# Sensor.net
KiCad netlist of a schematic drawn in Altium Designer
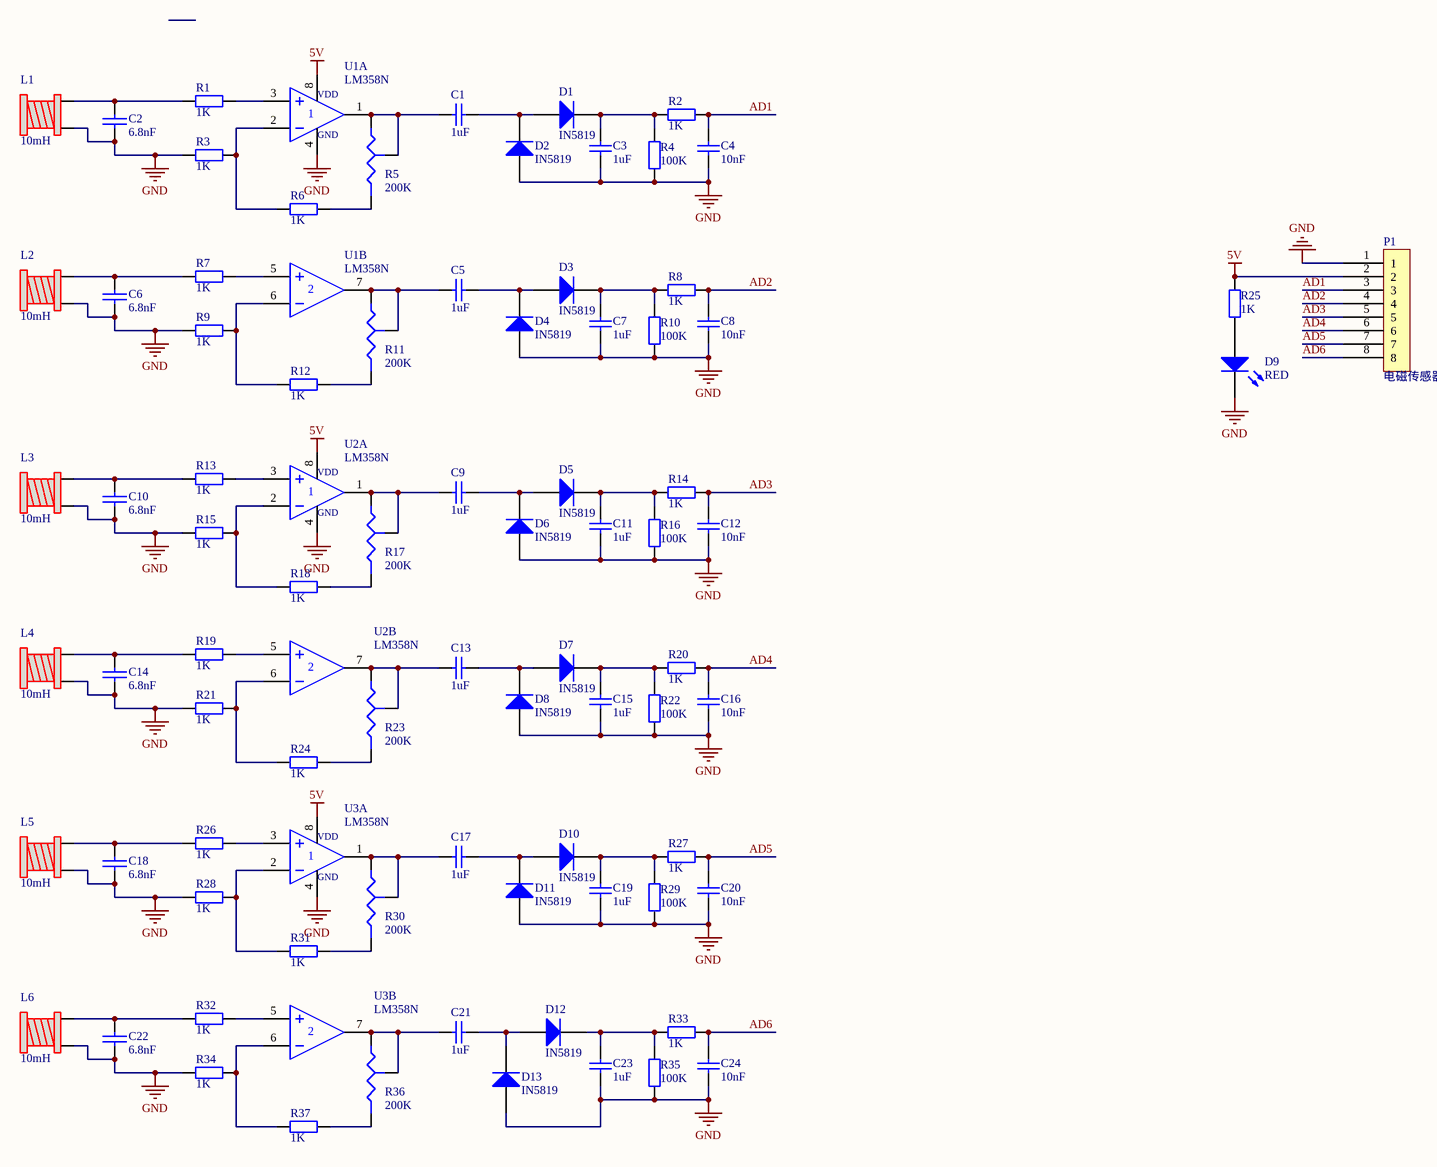
[diagram p0: Sensor.SchDoc]

(export (version "E")
  (design (tool "Eeschema 10.0.6"))
  (components
    (comp (ref "C1") (value "1uF") (footprint "0603C") (libsource (lib "1209Lab") (part "CAP")))
    (comp (ref "C2")
      (value "6.8nF")
      (footprint "0603C")
      (description "Capacitor")
      (libsource (lib "电磁放大器模块") (part "6.8μF"))
    )
    (comp (ref "C3") (value "1uF") (footprint "0603C") (libsource (lib "1209Lab") (part "CAP")))
    (comp (ref "C4") (value "10nF") (footprint "0603C") (libsource (lib "1209Lab") (part "CAP")))
    (comp (ref "C5") (value "1uF") (footprint "0603C") (libsource (lib "1209Lab") (part "CAP")))
    (comp (ref "C6")
      (value "6.8nF")
      (footprint "0603C")
      (description "Capacitor")
      (libsource (lib "电磁放大器模块") (part "6.8μF"))
    )
    (comp (ref "C7") (value "1uF") (footprint "0603C") (libsource (lib "1209Lab") (part "CAP")))
    (comp (ref "C8") (value "10nF") (footprint "0603C") (libsource (lib "1209Lab") (part "CAP")))
    (comp (ref "C9") (value "1uF") (footprint "0603C") (libsource (lib "1209Lab") (part "CAP")))
    (comp (ref "C10")
      (value "6.8nF")
      (footprint "0603C")
      (description "Capacitor")
      (libsource (lib "电磁放大器模块") (part "6.8μF"))
    )
    (comp (ref "C11") (value "1uF") (footprint "0603C") (libsource (lib "1209Lab") (part "CAP")))
    (comp (ref "C12") (value "10nF") (footprint "0603C") (libsource (lib "1209Lab") (part "CAP")))
    (comp (ref "C13") (value "1uF") (footprint "0603C") (libsource (lib "1209Lab") (part "CAP")))
    (comp (ref "C14")
      (value "6.8nF")
      (footprint "0603C")
      (description "Capacitor")
      (libsource (lib "电磁放大器模块") (part "6.8μF"))
    )
    (comp (ref "C15") (value "1uF") (footprint "0603C") (libsource (lib "1209Lab") (part "CAP")))
    (comp (ref "C16") (value "10nF") (footprint "0603C") (libsource (lib "1209Lab") (part "CAP")))
    (comp (ref "C17") (value "1uF") (footprint "0603C") (libsource (lib "1209Lab") (part "CAP")))
    (comp (ref "C18")
      (value "6.8nF")
      (footprint "0603C")
      (description "Capacitor")
      (libsource (lib "电磁放大器模块") (part "6.8μF"))
    )
    (comp (ref "C19") (value "1uF") (footprint "0603C") (libsource (lib "1209Lab") (part "CAP")))
    (comp (ref "C20") (value "10nF") (footprint "0603C") (libsource (lib "1209Lab") (part "CAP")))
    (comp (ref "C21") (value "1uF") (footprint "0603C") (libsource (lib "1209Lab") (part "CAP")))
    (comp (ref "C22")
      (value "6.8nF")
      (footprint "0603C")
      (description "Capacitor")
      (libsource (lib "电磁放大器模块") (part "6.8μF"))
    )
    (comp (ref "C23") (value "1uF") (footprint "0603C") (libsource (lib "1209Lab") (part "CAP")))
    (comp (ref "C24") (value "10nF") (footprint "0603C") (libsource (lib "1209Lab") (part "CAP")))
    (comp (ref "D1")
      (value "IN5819")
      (footprint "DL-41 - duplicate")
      (description "Default Diode")
      (libsource (lib "MOS motor driving module ") (part "Diode"))
    )
    (comp (ref "D2")
      (value "IN5819")
      (footprint "DL-41 - duplicate")
      (description "Default Diode")
      (libsource (lib "MOS motor driving module ") (part "Diode"))
    )
    (comp (ref "D3")
      (value "IN5819")
      (footprint "DL-41 - duplicate")
      (description "Default Diode")
      (libsource (lib "MOS motor driving module ") (part "Diode"))
    )
    (comp (ref "D4")
      (value "IN5819")
      (footprint "DL-41 - duplicate")
      (description "Default Diode")
      (libsource (lib "MOS motor driving module ") (part "Diode"))
    )
    (comp (ref "D5")
      (value "IN5819")
      (footprint "DL-41 - duplicate")
      (description "Default Diode")
      (libsource (lib "MOS motor driving module ") (part "Diode"))
    )
    (comp (ref "D6")
      (value "IN5819")
      (footprint "DL-41 - duplicate")
      (description "Default Diode")
      (libsource (lib "MOS motor driving module ") (part "Diode"))
    )
    (comp (ref "D7")
      (value "IN5819")
      (footprint "DL-41 - duplicate")
      (description "Default Diode")
      (libsource (lib "MOS motor driving module ") (part "Diode"))
    )
    (comp (ref "D8")
      (value "IN5819")
      (footprint "DL-41 - duplicate")
      (description "Default Diode")
      (libsource (lib "MOS motor driving module ") (part "Diode"))
    )
    (comp (ref "D9")
      (value "RED")
      (footprint "0805LED")
      (description "Typical RED, GREEN, YELLOW, AMBER GaAs LED")
      (fields (field (name "PUBLISHER") "Altium Limited"))
      (libsource (lib "MOS motor driving module ") (part "LED2"))
    )
    (comp (ref "D10")
      (value "IN5819")
      (footprint "DL-41 - duplicate")
      (description "Default Diode")
      (libsource (lib "MOS motor driving module ") (part "Diode"))
    )
    (comp (ref "D11")
      (value "IN5819")
      (footprint "DL-41 - duplicate")
      (description "Default Diode")
      (libsource (lib "MOS motor driving module ") (part "Diode"))
    )
    (comp (ref "D12")
      (value "IN5819")
      (footprint "DL-41 - duplicate")
      (description "Default Diode")
      (libsource (lib "MOS motor driving module ") (part "Diode"))
    )
    (comp (ref "D13")
      (value "IN5819")
      (footprint "DL-41 - duplicate")
      (description "Default Diode")
      (libsource (lib "MOS motor driving module ") (part "Diode"))
    )
    (comp (ref "L1") (value "10mH") (footprint "6X8mm电感") (libsource (lib "电磁放大器模块") (part "Inductor_1")))
    (comp (ref "L2") (value "10mH") (footprint "6X8mm电感") (libsource (lib "电磁放大器模块") (part "Inductor_1")))
    (comp (ref "L3") (value "10mH") (footprint "6X8mm电感") (libsource (lib "电磁放大器模块") (part "Inductor_1")))
    (comp (ref "L4") (value "10mH") (footprint "6X8mm电感") (libsource (lib "电磁放大器模块") (part "Inductor_1")))
    (comp (ref "L5") (value "10mH") (footprint "6X8mm电感") (libsource (lib "电磁放大器模块") (part "Inductor_1")))
    (comp (ref "L6") (value "10mH") (footprint "6X8mm电感") (libsource (lib "电磁放大器模块") (part "Inductor_1")))
    (comp (ref "P1")
      (value "电磁传感器")
      (footprint "XH2.54_8P")
      (description "Header, 4-Pin, Dual row")
      (fields (field (name "PUBLISHER") "Altium Limited"))
      (libsource (lib "蓝宙电子锋速系列主板封装库") (part "Header 8X1A"))
    )
    (comp (ref "R1")
      (value "1K")
      (footprint "0603-1")
      (description "Resistor贴片封装")
      (fields (field (name "Comment") "Res2") (field (name "PUBLISHER") "Altium Limited"))
      (libsource (lib "My") (part "Res2"))
    )
    (comp (ref "R2")
      (value "1K")
      (footprint "0603-1")
      (description "Resistor贴片封装")
      (fields (field (name "Comment") "Res2") (field (name "PUBLISHER") "Altium Limited"))
      (libsource (lib "") (part "Res2_1"))
    )
    (comp (ref "R3")
      (value "1K")
      (footprint "0603-1")
      (description "Resistor贴片封装")
      (fields (field (name "Comment") "Res2") (field (name "PUBLISHER") "Altium Limited"))
      (libsource (lib "My") (part "Res2"))
    )
    (comp (ref "R4")
      (value "100K")
      (footprint "0603-1")
      (description "Resistor贴片封装")
      (fields (field (name "Comment") "Res2") (field (name "PUBLISHER") "Altium Limited"))
      (libsource (lib "") (part "Res2_2"))
    )
    (comp (ref "R5") (value "200K") (footprint "VR_3362P") (libsource (lib "1209Lab") (part "RES-ADJ")))
    (comp (ref "R6")
      (value "1K")
      (footprint "0603-1")
      (description "Resistor贴片封装")
      (fields (field (name "Comment") "Res2") (field (name "PUBLISHER") "Altium Limited"))
      (libsource (lib "My") (part "Res2"))
    )
    (comp (ref "R7")
      (value "1K")
      (footprint "0603-1")
      (description "Resistor贴片封装")
      (fields (field (name "Comment") "Res2") (field (name "PUBLISHER") "Altium Limited"))
      (libsource (lib "My") (part "Res2"))
    )
    (comp (ref "R8")
      (value "1K")
      (footprint "0603-1")
      (description "Resistor贴片封装")
      (fields (field (name "Comment") "Res2") (field (name "PUBLISHER") "Altium Limited"))
      (libsource (lib "") (part "Res2_1"))
    )
    (comp (ref "R9")
      (value "1K")
      (footprint "0603-1")
      (description "Resistor贴片封装")
      (fields (field (name "Comment") "Res2") (field (name "PUBLISHER") "Altium Limited"))
      (libsource (lib "My") (part "Res2"))
    )
    (comp (ref "R10")
      (value "100K")
      (footprint "0603-1")
      (description "Resistor贴片封装")
      (fields (field (name "Comment") "Res2") (field (name "PUBLISHER") "Altium Limited"))
      (libsource (lib "") (part "Res2_2"))
    )
    (comp (ref "R11") (value "200K") (footprint "VR_3362P") (libsource (lib "1209Lab") (part "RES-ADJ")))
    (comp (ref "R12")
      (value "1K")
      (footprint "0603-1")
      (description "Resistor贴片封装")
      (fields (field (name "Comment") "Res2") (field (name "PUBLISHER") "Altium Limited"))
      (libsource (lib "My") (part "Res2"))
    )
    (comp (ref "R13")
      (value "1K")
      (footprint "0603-1")
      (description "Resistor贴片封装")
      (fields (field (name "Comment") "Res2") (field (name "PUBLISHER") "Altium Limited"))
      (libsource (lib "My") (part "Res2"))
    )
    (comp (ref "R14")
      (value "1K")
      (footprint "0603-1")
      (description "Resistor贴片封装")
      (fields (field (name "Comment") "Res2") (field (name "PUBLISHER") "Altium Limited"))
      (libsource (lib "") (part "Res2_1"))
    )
    (comp (ref "R15")
      (value "1K")
      (footprint "0603-1")
      (description "Resistor贴片封装")
      (fields (field (name "Comment") "Res2") (field (name "PUBLISHER") "Altium Limited"))
      (libsource (lib "My") (part "Res2"))
    )
    (comp (ref "R16")
      (value "100K")
      (footprint "0603-1")
      (description "Resistor贴片封装")
      (fields (field (name "Comment") "Res2") (field (name "PUBLISHER") "Altium Limited"))
      (libsource (lib "") (part "Res2_2"))
    )
    (comp (ref "R17") (value "200K") (footprint "VR_3362P") (libsource (lib "1209Lab") (part "RES-ADJ")))
    (comp (ref "R18")
      (value "1K")
      (footprint "0603-1")
      (description "Resistor贴片封装")
      (fields (field (name "Comment") "Res2") (field (name "PUBLISHER") "Altium Limited"))
      (libsource (lib "My") (part "Res2"))
    )
    (comp (ref "R19")
      (value "1K")
      (footprint "0603-1")
      (description "Resistor贴片封装")
      (fields (field (name "Comment") "Res2") (field (name "PUBLISHER") "Altium Limited"))
      (libsource (lib "My") (part "Res2"))
    )
    (comp (ref "R20")
      (value "1K")
      (footprint "0603-1")
      (description "Resistor贴片封装")
      (fields (field (name "Comment") "Res2") (field (name "PUBLISHER") "Altium Limited"))
      (libsource (lib "") (part "Res2_1"))
    )
    (comp (ref "R21")
      (value "1K")
      (footprint "0603-1")
      (description "Resistor贴片封装")
      (fields (field (name "Comment") "Res2") (field (name "PUBLISHER") "Altium Limited"))
      (libsource (lib "My") (part "Res2"))
    )
    (comp (ref "R22")
      (value "100K")
      (footprint "0603-1")
      (description "Resistor贴片封装")
      (fields (field (name "Comment") "Res2") (field (name "PUBLISHER") "Altium Limited"))
      (libsource (lib "") (part "Res2_2"))
    )
    (comp (ref "R23") (value "200K") (footprint "VR_3362P") (libsource (lib "1209Lab") (part "RES-ADJ")))
    (comp (ref "R24")
      (value "1K")
      (footprint "0603-1")
      (description "Resistor贴片封装")
      (fields (field (name "Comment") "Res2") (field (name "PUBLISHER") "Altium Limited"))
      (libsource (lib "My") (part "Res2"))
    )
    (comp (ref "R25")
      (value "1K")
      (footprint "0603-1")
      (description "Resistor贴片封装")
      (fields (field (name "Comment") "Res2") (field (name "PUBLISHER") "Altium Limited"))
      (libsource (lib "") (part "Res2_3"))
    )
    (comp (ref "R26")
      (value "1K")
      (footprint "0603-1")
      (description "Resistor贴片封装")
      (fields (field (name "Comment") "Res2") (field (name "PUBLISHER") "Altium Limited"))
      (libsource (lib "My") (part "Res2"))
    )
    (comp (ref "R27")
      (value "1K")
      (footprint "0603-1")
      (description "Resistor贴片封装")
      (fields (field (name "Comment") "Res2") (field (name "PUBLISHER") "Altium Limited"))
      (libsource (lib "") (part "Res2_1"))
    )
    (comp (ref "R28")
      (value "1K")
      (footprint "0603-1")
      (description "Resistor贴片封装")
      (fields (field (name "Comment") "Res2") (field (name "PUBLISHER") "Altium Limited"))
      (libsource (lib "My") (part "Res2"))
    )
    (comp (ref "R29")
      (value "100K")
      (footprint "0603-1")
      (description "Resistor贴片封装")
      (fields (field (name "Comment") "Res2") (field (name "PUBLISHER") "Altium Limited"))
      (libsource (lib "") (part "Res2_2"))
    )
    (comp (ref "R30") (value "200K") (footprint "VR_3362P") (libsource (lib "1209Lab") (part "RES-ADJ")))
    (comp (ref "R31")
      (value "1K")
      (footprint "0603-1")
      (description "Resistor贴片封装")
      (fields (field (name "Comment") "Res2") (field (name "PUBLISHER") "Altium Limited"))
      (libsource (lib "My") (part "Res2"))
    )
    (comp (ref "R32")
      (value "1K")
      (footprint "0603-1")
      (description "Resistor贴片封装")
      (fields (field (name "Comment") "Res2") (field (name "PUBLISHER") "Altium Limited"))
      (libsource (lib "My") (part "Res2"))
    )
    (comp (ref "R33")
      (value "1K")
      (footprint "0603-1")
      (description "Resistor贴片封装")
      (fields (field (name "Comment") "Res2") (field (name "PUBLISHER") "Altium Limited"))
      (libsource (lib "") (part "Res2_1"))
    )
    (comp (ref "R34")
      (value "1K")
      (footprint "0603-1")
      (description "Resistor贴片封装")
      (fields (field (name "Comment") "Res2") (field (name "PUBLISHER") "Altium Limited"))
      (libsource (lib "My") (part "Res2"))
    )
    (comp (ref "R35")
      (value "100K")
      (footprint "0603-1")
      (description "Resistor贴片封装")
      (fields (field (name "Comment") "Res2") (field (name "PUBLISHER") "Altium Limited"))
      (libsource (lib "") (part "Res2_2"))
    )
    (comp (ref "R36") (value "200K") (footprint "VR_3362P") (libsource (lib "1209Lab") (part "RES-ADJ")))
    (comp (ref "R37")
      (value "1K")
      (footprint "0603-1")
      (description "Resistor贴片封装")
      (fields (field (name "Comment") "Res2") (field (name "PUBLISHER") "Altium Limited"))
      (libsource (lib "My") (part "Res2"))
    )
    (comp (ref "U1")
      (value "LM358N")
      (footprint "SOIC-8")
      (description "Dual Low-Power Operational Amplifier")
      (libsource (lib "电磁放大器模块") (part "LM358N"))
    )
    (comp (ref "U2")
      (value "LM358N")
      (footprint "SOIC-8")
      (description "Dual Low-Power Operational Amplifier")
      (libsource (lib "电磁放大器模块") (part "LM358N"))
    )
    (comp (ref "U3")
      (value "LM358N")
      (footprint "SOIC-8")
      (description "Dual Low-Power Operational Amplifier")
      (libsource (lib "电磁放大器模块") (part "LM358N"))
    )
  )
  (nets
    (net (code "1") (name "/AD1") (class "Default")
      (node (ref "C4") (pin "1") (pinfunction "1_1") (pintype "passive"))
      (node (ref "P1") (pin "3") (pinfunction "3_3") (pintype "passive"))
      (node (ref "R2") (pin "1") (pinfunction "1_1") (pintype "passive"))
    )
    (net (code "2") (name "/AD2") (class "Default")
      (node (ref "C8") (pin "1") (pinfunction "1_1") (pintype "passive"))
      (node (ref "P1") (pin "4") (pinfunction "4_4") (pintype "passive"))
      (node (ref "R8") (pin "1") (pinfunction "1_1") (pintype "passive"))
    )
    (net (code "3") (name "/AD3") (class "Default")
      (node (ref "C12") (pin "1") (pinfunction "1_1") (pintype "passive"))
      (node (ref "P1") (pin "5") (pinfunction "5_5") (pintype "passive"))
      (node (ref "R14") (pin "1") (pinfunction "1_1") (pintype "passive"))
    )
    (net (code "4") (name "/AD4") (class "Default")
      (node (ref "C16") (pin "1") (pinfunction "1_1") (pintype "passive"))
      (node (ref "P1") (pin "6") (pinfunction "6_6") (pintype "passive"))
      (node (ref "R20") (pin "1") (pinfunction "1_1") (pintype "passive"))
    )
    (net (code "5") (name "/AD5") (class "Default")
      (node (ref "C20") (pin "1") (pinfunction "1_1") (pintype "passive"))
      (node (ref "P1") (pin "7") (pinfunction "7_7") (pintype "passive"))
      (node (ref "R27") (pin "1") (pinfunction "1_1") (pintype "passive"))
    )
    (net (code "6") (name "/AD6") (class "Default")
      (node (ref "C24") (pin "1") (pinfunction "1_1") (pintype "passive"))
      (node (ref "P1") (pin "8") (pinfunction "8_8") (pintype "passive"))
      (node (ref "R33") (pin "1") (pinfunction "1_1") (pintype "passive"))
    )
    (net (code "7") (name "5V") (class "Default")
      (node (ref "P1") (pin "2") (pinfunction "2_2") (pintype "passive"))
      (node (ref "R25") (pin "1") (pinfunction "1_1") (pintype "passive"))
      (node (ref "U1") (pin "8") (pinfunction "VDD_8") (pintype "passive"))
      (node (ref "U2") (pin "8") (pinfunction "VDD_8") (pintype "passive"))
      (node (ref "U3") (pin "8") (pinfunction "VDD_8") (pintype "passive"))
    )
    (net (code "8") (name "GND") (class "Default")
      (node (ref "C10") (pin "2") (pinfunction "2_2") (pintype "passive"))
      (node (ref "C11") (pin "2") (pinfunction "2_2") (pintype "passive"))
      (node (ref "C12") (pin "2") (pinfunction "2_2") (pintype "passive"))
      (node (ref "C14") (pin "2") (pinfunction "2_2") (pintype "passive"))
      (node (ref "C15") (pin "2") (pinfunction "2_2") (pintype "passive"))
      (node (ref "C16") (pin "2") (pinfunction "2_2") (pintype "passive"))
      (node (ref "C18") (pin "2") (pinfunction "2_2") (pintype "passive"))
      (node (ref "C19") (pin "2") (pinfunction "2_2") (pintype "passive"))
      (node (ref "C2") (pin "2") (pinfunction "2_2") (pintype "passive"))
      (node (ref "C20") (pin "2") (pinfunction "2_2") (pintype "passive"))
      (node (ref "C22") (pin "2") (pinfunction "2_2") (pintype "passive"))
      (node (ref "C23") (pin "2") (pinfunction "2_2") (pintype "passive"))
      (node (ref "C24") (pin "2") (pinfunction "2_2") (pintype "passive"))
      (node (ref "C3") (pin "2") (pinfunction "2_2") (pintype "passive"))
      (node (ref "C4") (pin "2") (pinfunction "2_2") (pintype "passive"))
      (node (ref "C6") (pin "2") (pinfunction "2_2") (pintype "passive"))
      (node (ref "C7") (pin "2") (pinfunction "2_2") (pintype "passive"))
      (node (ref "C8") (pin "2") (pinfunction "2_2") (pintype "passive"))
      (node (ref "D11") (pin "1") (pinfunction "A_1") (pintype "passive"))
      (node (ref "D13") (pin "1") (pinfunction "A_1") (pintype "passive"))
      (node (ref "D2") (pin "1") (pinfunction "A_1") (pintype "passive"))
      (node (ref "D4") (pin "1") (pinfunction "A_1") (pintype "passive"))
      (node (ref "D6") (pin "1") (pinfunction "A_1") (pintype "passive"))
      (node (ref "D8") (pin "1") (pinfunction "A_1") (pintype "passive"))
      (node (ref "D9") (pin "2") (pinfunction "K_2") (pintype "passive"))
      (node (ref "L1") (pin "1") (pinfunction "1_1") (pintype "passive"))
      (node (ref "L2") (pin "1") (pinfunction "1_1") (pintype "passive"))
      (node (ref "L3") (pin "1") (pinfunction "1_1") (pintype "passive"))
      (node (ref "L4") (pin "1") (pinfunction "1_1") (pintype "passive"))
      (node (ref "L5") (pin "1") (pinfunction "1_1") (pintype "passive"))
      (node (ref "L6") (pin "1") (pinfunction "1_1") (pintype "passive"))
      (node (ref "P1") (pin "1") (pinfunction "1_1") (pintype "passive"))
      (node (ref "R10") (pin "1") (pinfunction "1_1") (pintype "passive"))
      (node (ref "R15") (pin "1") (pinfunction "1_1") (pintype "passive"))
      (node (ref "R16") (pin "1") (pinfunction "1_1") (pintype "passive"))
      (node (ref "R21") (pin "1") (pinfunction "1_1") (pintype "passive"))
      (node (ref "R22") (pin "1") (pinfunction "1_1") (pintype "passive"))
      (node (ref "R28") (pin "1") (pinfunction "1_1") (pintype "passive"))
      (node (ref "R29") (pin "1") (pinfunction "1_1") (pintype "passive"))
      (node (ref "R3") (pin "1") (pinfunction "1_1") (pintype "passive"))
      (node (ref "R34") (pin "1") (pinfunction "1_1") (pintype "passive"))
      (node (ref "R35") (pin "1") (pinfunction "1_1") (pintype "passive"))
      (node (ref "R4") (pin "1") (pinfunction "1_1") (pintype "passive"))
      (node (ref "R9") (pin "1") (pinfunction "1_1") (pintype "passive"))
      (node (ref "U1") (pin "4") (pinfunction "GND_4") (pintype "passive"))
      (node (ref "U2") (pin "4") (pinfunction "GND_4") (pintype "passive"))
      (node (ref "U3") (pin "4") (pinfunction "GND_4") (pintype "passive"))
    )
    (net (code "9") (name "Net-(C2-Pad1)") (class "Default")
      (node (ref "C2") (pin "1") (pinfunction "1_1") (pintype "passive"))
      (node (ref "L1") (pin "2") (pinfunction "2_2") (pintype "passive"))
      (node (ref "R1") (pin "1") (pinfunction "1_1") (pintype "passive"))
    )
    (net (code "10") (name "Net-(C6-Pad1)") (class "Default")
      (node (ref "C6") (pin "1") (pinfunction "1_1") (pintype "passive"))
      (node (ref "L2") (pin "2") (pinfunction "2_2") (pintype "passive"))
      (node (ref "R7") (pin "1") (pinfunction "1_1") (pintype "passive"))
    )
    (net (code "11") (name "Net-(C10-Pad1)") (class "Default")
      (node (ref "C10") (pin "1") (pinfunction "1_1") (pintype "passive"))
      (node (ref "L3") (pin "2") (pinfunction "2_2") (pintype "passive"))
      (node (ref "R13") (pin "1") (pinfunction "1_1") (pintype "passive"))
    )
    (net (code "12") (name "Net-(C14-Pad1)") (class "Default")
      (node (ref "C14") (pin "1") (pinfunction "1_1") (pintype "passive"))
      (node (ref "L4") (pin "2") (pinfunction "2_2") (pintype "passive"))
      (node (ref "R19") (pin "1") (pinfunction "1_1") (pintype "passive"))
    )
    (net (code "13") (name "Net-(C18-Pad1)") (class "Default")
      (node (ref "C18") (pin "1") (pinfunction "1_1") (pintype "passive"))
      (node (ref "L5") (pin "2") (pinfunction "2_2") (pintype "passive"))
      (node (ref "R26") (pin "1") (pinfunction "1_1") (pintype "passive"))
    )
    (net (code "14") (name "Net-(C22-Pad1)") (class "Default")
      (node (ref "C22") (pin "1") (pinfunction "1_1") (pintype "passive"))
      (node (ref "L6") (pin "2") (pinfunction "2_2") (pintype "passive"))
      (node (ref "R32") (pin "1") (pinfunction "1_1") (pintype "passive"))
    )
    (net (code "15") (name "Net-(D1-A)") (class "Default")
      (node (ref "C1") (pin "1") (pinfunction "1_1") (pintype "passive"))
      (node (ref "D1") (pin "1") (pinfunction "A_1") (pintype "passive"))
      (node (ref "D2") (pin "2") (pinfunction "K_2") (pintype "passive"))
    )
    (net (code "16") (name "Net-(D1-K)") (class "Default")
      (node (ref "C3") (pin "1") (pinfunction "1_1") (pintype "passive"))
      (node (ref "D1") (pin "2") (pinfunction "K_2") (pintype "passive"))
      (node (ref "R2") (pin "2") (pinfunction "2_2") (pintype "passive"))
      (node (ref "R4") (pin "2") (pinfunction "2_2") (pintype "passive"))
    )
    (net (code "17") (name "Net-(D3-A)") (class "Default")
      (node (ref "C5") (pin "1") (pinfunction "1_1") (pintype "passive"))
      (node (ref "D3") (pin "1") (pinfunction "A_1") (pintype "passive"))
      (node (ref "D4") (pin "2") (pinfunction "K_2") (pintype "passive"))
    )
    (net (code "18") (name "Net-(D3-K)") (class "Default")
      (node (ref "C7") (pin "1") (pinfunction "1_1") (pintype "passive"))
      (node (ref "D3") (pin "2") (pinfunction "K_2") (pintype "passive"))
      (node (ref "R10") (pin "2") (pinfunction "2_2") (pintype "passive"))
      (node (ref "R8") (pin "2") (pinfunction "2_2") (pintype "passive"))
    )
    (net (code "19") (name "Net-(D5-A)") (class "Default")
      (node (ref "C9") (pin "1") (pinfunction "1_1") (pintype "passive"))
      (node (ref "D5") (pin "1") (pinfunction "A_1") (pintype "passive"))
      (node (ref "D6") (pin "2") (pinfunction "K_2") (pintype "passive"))
    )
    (net (code "20") (name "Net-(D5-K)") (class "Default")
      (node (ref "C11") (pin "1") (pinfunction "1_1") (pintype "passive"))
      (node (ref "D5") (pin "2") (pinfunction "K_2") (pintype "passive"))
      (node (ref "R14") (pin "2") (pinfunction "2_2") (pintype "passive"))
      (node (ref "R16") (pin "2") (pinfunction "2_2") (pintype "passive"))
    )
    (net (code "21") (name "Net-(D7-A)") (class "Default")
      (node (ref "C13") (pin "1") (pinfunction "1_1") (pintype "passive"))
      (node (ref "D7") (pin "1") (pinfunction "A_1") (pintype "passive"))
      (node (ref "D8") (pin "2") (pinfunction "K_2") (pintype "passive"))
    )
    (net (code "22") (name "Net-(D7-K)") (class "Default")
      (node (ref "C15") (pin "1") (pinfunction "1_1") (pintype "passive"))
      (node (ref "D7") (pin "2") (pinfunction "K_2") (pintype "passive"))
      (node (ref "R20") (pin "2") (pinfunction "2_2") (pintype "passive"))
      (node (ref "R22") (pin "2") (pinfunction "2_2") (pintype "passive"))
    )
    (net (code "23") (name "Net-(D9-A)") (class "Default")
      (node (ref "D9") (pin "1") (pinfunction "A_1") (pintype "passive"))
      (node (ref "R25") (pin "2") (pinfunction "2_2") (pintype "passive"))
    )
    (net (code "24") (name "Net-(D10-A)") (class "Default")
      (node (ref "C17") (pin "1") (pinfunction "1_1") (pintype "passive"))
      (node (ref "D10") (pin "1") (pinfunction "A_1") (pintype "passive"))
      (node (ref "D11") (pin "2") (pinfunction "K_2") (pintype "passive"))
    )
    (net (code "25") (name "Net-(D10-K)") (class "Default")
      (node (ref "C19") (pin "1") (pinfunction "1_1") (pintype "passive"))
      (node (ref "D10") (pin "2") (pinfunction "K_2") (pintype "passive"))
      (node (ref "R27") (pin "2") (pinfunction "2_2") (pintype "passive"))
      (node (ref "R29") (pin "2") (pinfunction "2_2") (pintype "passive"))
    )
    (net (code "26") (name "Net-(D12-A)") (class "Default")
      (node (ref "C21") (pin "1") (pinfunction "1_1") (pintype "passive"))
      (node (ref "D12") (pin "1") (pinfunction "A_1") (pintype "passive"))
      (node (ref "D13") (pin "2") (pinfunction "K_2") (pintype "passive"))
    )
    (net (code "27") (name "Net-(D12-K)") (class "Default")
      (node (ref "C23") (pin "1") (pinfunction "1_1") (pintype "passive"))
      (node (ref "D12") (pin "2") (pinfunction "K_2") (pintype "passive"))
      (node (ref "R33") (pin "2") (pinfunction "2_2") (pintype "passive"))
      (node (ref "R35") (pin "2") (pinfunction "2_2") (pintype "passive"))
    )
    (net (code "28") (name "Net-(R5-Pad3)") (class "Default")
      (node (ref "R5") (pin "3") (pinfunction "3_3") (pintype "passive"))
      (node (ref "R6") (pin "2") (pinfunction "2_2") (pintype "passive"))
    )
    (net (code "29") (name "Net-(R11-Pad3)") (class "Default")
      (node (ref "R11") (pin "3") (pinfunction "3_3") (pintype "passive"))
      (node (ref "R12") (pin "2") (pinfunction "2_2") (pintype "passive"))
    )
    (net (code "30") (name "Net-(R17-Pad3)") (class "Default")
      (node (ref "R17") (pin "3") (pinfunction "3_3") (pintype "passive"))
      (node (ref "R18") (pin "2") (pinfunction "2_2") (pintype "passive"))
    )
    (net (code "31") (name "Net-(R23-Pad3)") (class "Default")
      (node (ref "R23") (pin "3") (pinfunction "3_3") (pintype "passive"))
      (node (ref "R24") (pin "2") (pinfunction "2_2") (pintype "passive"))
    )
    (net (code "32") (name "Net-(R30-Pad3)") (class "Default")
      (node (ref "R30") (pin "3") (pinfunction "3_3") (pintype "passive"))
      (node (ref "R31") (pin "2") (pinfunction "2_2") (pintype "passive"))
    )
    (net (code "33") (name "Net-(R36-Pad3)") (class "Default")
      (node (ref "R36") (pin "3") (pinfunction "3_3") (pintype "passive"))
      (node (ref "R37") (pin "2") (pinfunction "2_2") (pintype "passive"))
    )
    (net (code "34") (name "Net-(U1A-IN+)") (class "Default")
      (node (ref "R1") (pin "2") (pinfunction "2_2") (pintype "passive"))
      (node (ref "U1") (pin "3") (pinfunction "IN+_3") (pintype "passive"))
    )
    (net (code "35") (name "Net-(U1A-IN-)") (class "Default")
      (node (ref "R3") (pin "2") (pinfunction "2_2") (pintype "passive"))
      (node (ref "R6") (pin "1") (pinfunction "1_1") (pintype "passive"))
      (node (ref "U1") (pin "2") (pinfunction "IN-_2") (pintype "passive"))
    )
    (net (code "36") (name "Net-(U1A-OUT)") (class "Default")
      (node (ref "C1") (pin "2") (pinfunction "2_2") (pintype "passive"))
      (node (ref "R5") (pin "1") (pinfunction "1_1") (pintype "passive"))
      (node (ref "R5") (pin "2") (pinfunction "2_2") (pintype "passive"))
      (node (ref "U1") (pin "1") (pinfunction "OUT_1") (pintype "passive"))
    )
    (net (code "37") (name "Net-(U1B-IN+)") (class "Default")
      (node (ref "R7") (pin "2") (pinfunction "2_2") (pintype "passive"))
      (node (ref "U1") (pin "5") (pinfunction "IN+_5") (pintype "passive"))
    )
    (net (code "38") (name "Net-(U1B-IN-)") (class "Default")
      (node (ref "R12") (pin "1") (pinfunction "1_1") (pintype "passive"))
      (node (ref "R9") (pin "2") (pinfunction "2_2") (pintype "passive"))
      (node (ref "U1") (pin "6") (pinfunction "IN-_6") (pintype "passive"))
    )
    (net (code "39") (name "Net-(U1B-OUT)") (class "Default")
      (node (ref "C5") (pin "2") (pinfunction "2_2") (pintype "passive"))
      (node (ref "R11") (pin "1") (pinfunction "1_1") (pintype "passive"))
      (node (ref "R11") (pin "2") (pinfunction "2_2") (pintype "passive"))
      (node (ref "U1") (pin "7") (pinfunction "OUT_7") (pintype "passive"))
    )
    (net (code "40") (name "Net-(U2A-IN+)") (class "Default")
      (node (ref "R13") (pin "2") (pinfunction "2_2") (pintype "passive"))
      (node (ref "U2") (pin "3") (pinfunction "IN+_3") (pintype "passive"))
    )
    (net (code "41") (name "Net-(U2A-IN-)") (class "Default")
      (node (ref "R15") (pin "2") (pinfunction "2_2") (pintype "passive"))
      (node (ref "R18") (pin "1") (pinfunction "1_1") (pintype "passive"))
      (node (ref "U2") (pin "2") (pinfunction "IN-_2") (pintype "passive"))
    )
    (net (code "42") (name "Net-(U2A-OUT)") (class "Default")
      (node (ref "C9") (pin "2") (pinfunction "2_2") (pintype "passive"))
      (node (ref "R17") (pin "1") (pinfunction "1_1") (pintype "passive"))
      (node (ref "R17") (pin "2") (pinfunction "2_2") (pintype "passive"))
      (node (ref "U2") (pin "1") (pinfunction "OUT_1") (pintype "passive"))
    )
    (net (code "43") (name "Net-(U2B-IN+)") (class "Default")
      (node (ref "R19") (pin "2") (pinfunction "2_2") (pintype "passive"))
      (node (ref "U2") (pin "5") (pinfunction "IN+_5") (pintype "passive"))
    )
    (net (code "44") (name "Net-(U2B-IN-)") (class "Default")
      (node (ref "R21") (pin "2") (pinfunction "2_2") (pintype "passive"))
      (node (ref "R24") (pin "1") (pinfunction "1_1") (pintype "passive"))
      (node (ref "U2") (pin "6") (pinfunction "IN-_6") (pintype "passive"))
    )
    (net (code "45") (name "Net-(U2B-OUT)") (class "Default")
      (node (ref "C13") (pin "2") (pinfunction "2_2") (pintype "passive"))
      (node (ref "R23") (pin "1") (pinfunction "1_1") (pintype "passive"))
      (node (ref "R23") (pin "2") (pinfunction "2_2") (pintype "passive"))
      (node (ref "U2") (pin "7") (pinfunction "OUT_7") (pintype "passive"))
    )
    (net (code "46") (name "Net-(U3A-IN+)") (class "Default")
      (node (ref "R26") (pin "2") (pinfunction "2_2") (pintype "passive"))
      (node (ref "U3") (pin "3") (pinfunction "IN+_3") (pintype "passive"))
    )
    (net (code "47") (name "Net-(U3A-IN-)") (class "Default")
      (node (ref "R28") (pin "2") (pinfunction "2_2") (pintype "passive"))
      (node (ref "R31") (pin "1") (pinfunction "1_1") (pintype "passive"))
      (node (ref "U3") (pin "2") (pinfunction "IN-_2") (pintype "passive"))
    )
    (net (code "48") (name "Net-(U3A-OUT)") (class "Default")
      (node (ref "C17") (pin "2") (pinfunction "2_2") (pintype "passive"))
      (node (ref "R30") (pin "1") (pinfunction "1_1") (pintype "passive"))
      (node (ref "R30") (pin "2") (pinfunction "2_2") (pintype "passive"))
      (node (ref "U3") (pin "1") (pinfunction "OUT_1") (pintype "passive"))
    )
    (net (code "49") (name "Net-(U3B-IN+)") (class "Default")
      (node (ref "R32") (pin "2") (pinfunction "2_2") (pintype "passive"))
      (node (ref "U3") (pin "5") (pinfunction "IN+_5") (pintype "passive"))
    )
    (net (code "50") (name "Net-(U3B-IN-)") (class "Default")
      (node (ref "R34") (pin "2") (pinfunction "2_2") (pintype "passive"))
      (node (ref "R37") (pin "1") (pinfunction "1_1") (pintype "passive"))
      (node (ref "U3") (pin "6") (pinfunction "IN-_6") (pintype "passive"))
    )
    (net (code "51") (name "Net-(U3B-OUT)") (class "Default")
      (node (ref "C21") (pin "2") (pinfunction "2_2") (pintype "passive"))
      (node (ref "R36") (pin "1") (pinfunction "1_1") (pintype "passive"))
      (node (ref "R36") (pin "2") (pinfunction "2_2") (pintype "passive"))
      (node (ref "U3") (pin "7") (pinfunction "OUT_7") (pintype "passive"))
    )
  )
)
